# Power.net
KiCad netlist of a schematic drawn in Altium Designer
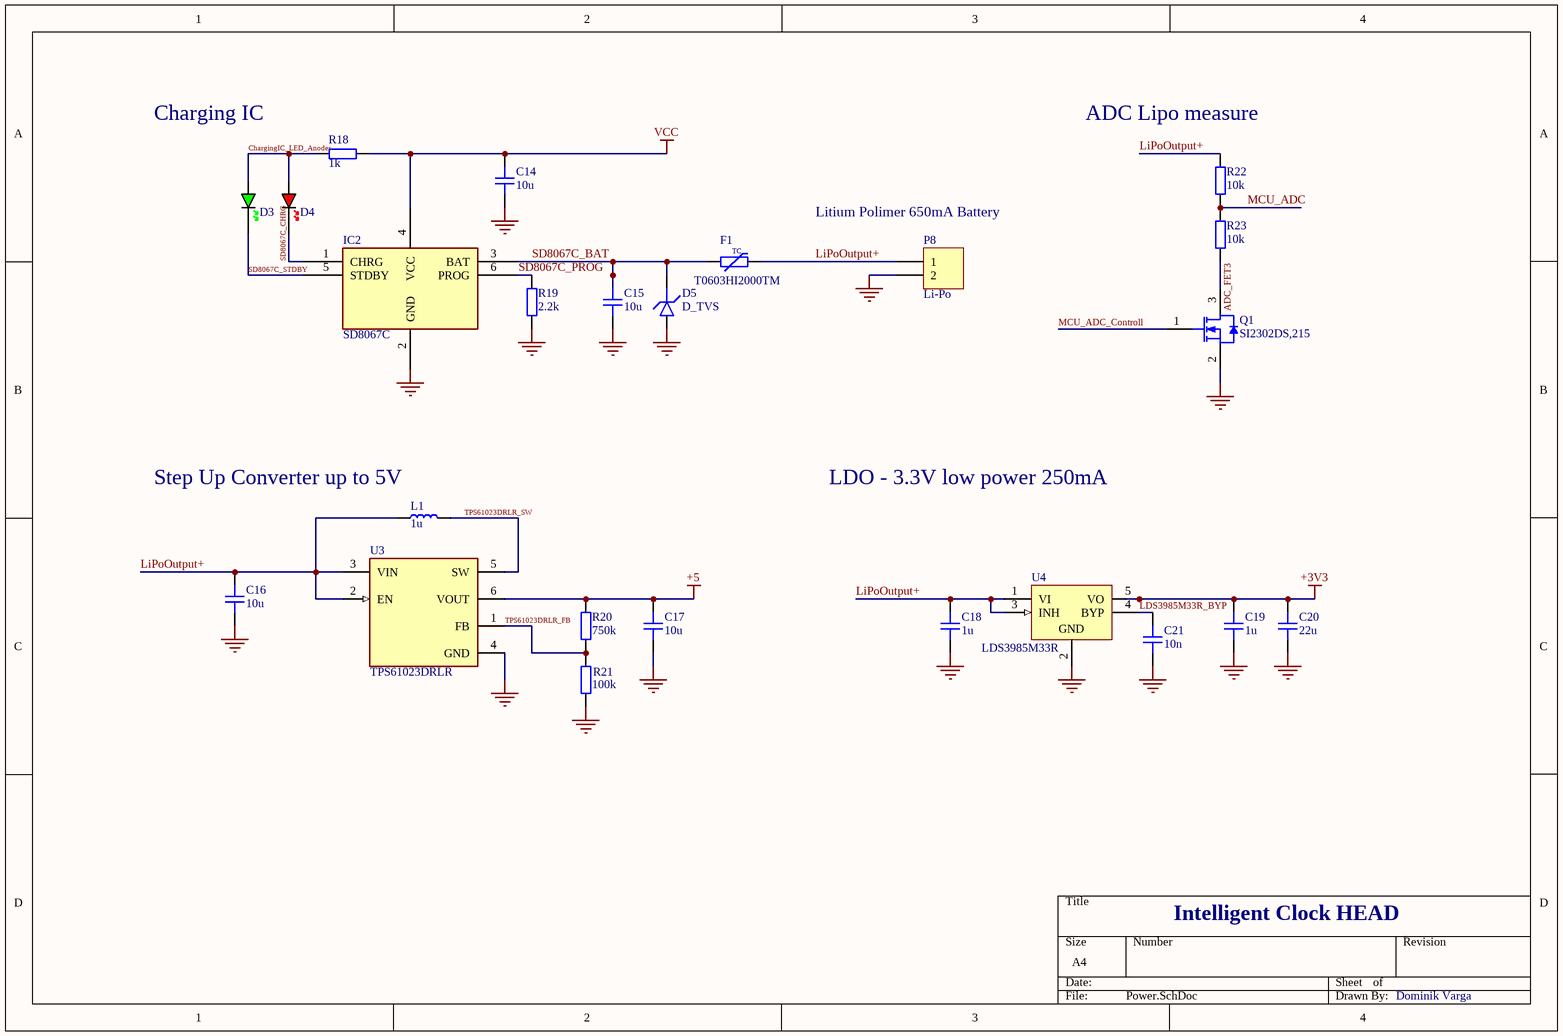
[diagram p0: Power.SchDoc]

(export (version "E")
  (design (tool "Eeschema 10.0.6"))
  (components
    (comp (ref "C14")
      (value "10u")
      (footprint "CAP_0603")
      (description "Capacitor SMD 0603 10V")
      (libsource (lib "Schematic-Lib-PhilsLab") (part "CAP_0603_10V"))
    )
    (comp (ref "C15")
      (value "10u")
      (footprint "CAP_0603")
      (description "Capacitor SMD 0603 10V")
      (libsource (lib "Schematic-Lib-PhilsLab") (part "CAP_0603_10V"))
    )
    (comp (ref "C16")
      (value "10u")
      (footprint "CAP_0603")
      (description "Capacitor SMD 0603 10V")
      (libsource (lib "Schematic-Lib-PhilsLab") (part "CAP_0603_10V"))
    )
    (comp (ref "C17")
      (value "10u")
      (footprint "CAP_0603")
      (description "Capacitor SMD 0603 10V")
      (libsource (lib "Schematic-Lib-PhilsLab") (part "CAP_0603_10V"))
    )
    (comp (ref "C18")
      (value "1u")
      (footprint "CAP_0603")
      (description "Capacitor SMD 0603 10V")
      (libsource (lib "Schematic-Lib-PhilsLab") (part "CAP_0603_10V"))
    )
    (comp (ref "C19")
      (value "1u")
      (footprint "CAP_0603")
      (description "Capacitor SMD 0603 10V")
      (libsource (lib "Schematic-Lib-PhilsLab") (part "CAP_0603_10V"))
    )
    (comp (ref "C20")
      (value "22u")
      (footprint "CAP_0603")
      (description "Capacitor SMD 0603 10V")
      (libsource (lib "Schematic-Lib-PhilsLab") (part "CAP_0603_10V"))
    )
    (comp (ref "C21")
      (value "10n")
      (footprint "CAP_0603")
      (description "Capacitor SMD 0603 10V")
      (libsource (lib "Schematic-Lib-PhilsLab") (part "CAP_0603_10V"))
    )
    (comp (ref "D3")
      (value "GREEN")
      (footprint "LED_0603_GREEN")
      (description "LED 0603 GREEN SMD")
      (libsource (lib "Schematic-Lib-PhilsLab") (part "LED_0603_GREEN"))
    )
    (comp (ref "D4")
      (value "RED")
      (footprint "LED_0603_RED")
      (description "LED 0603 RED SMD")
      (libsource (lib "Schematic-Lib-PhilsLab") (part "LED_0603_RED"))
    )
    (comp (ref "D5")
      (value "D_TVS")
      (footprint "DIOM2718X14N")
      (description "Diode TVS / ESD 0603")
      (libsource (lib "OnlabComponents") (part "D_TVS_0603"))
    )
    (comp (ref "F1")
      (value "T0603HI2000TM")
      (footprint "RESC1608X06N")
      (description "Fuse SMD 0603")
      (fields (field (name "MANUFACTURER") "AEM"))
      (libsource (lib "OnlabComponents") (part "FUSE_0603"))
    )
    (comp (ref "IC2")
      (value "SD8067C")
      (footprint "SOT95P280X125-6N")
      (description "Integrated Circuit, charging circuit")
      (fields (field (name "MANUFACTURER") "Shouding"))
      (libsource (lib "OnlabComponents") (part "SD8067C"))
    )
    (comp (ref "L1")
      (value "1u")
      (footprint "IND_1210")
      (description "Inductor SMD 1210")
      (libsource (lib "OnlabComponents") (part "IND_1210"))
    )
    (comp (ref "P8")
      (value "Li-Po")
      (footprint "HDR1X2H")
      (description "Header, 2-Pin, Right Angle")
      (fields (field (name "PUBLISHER") "Altium Limited"))
      (libsource (lib "Miscellaneous Connectors") (part "Header 2H"))
    )
    (comp (ref "Q1")
      (value "SI2302DS,215")
      (footprint "NXP-SOT23_N")
      (description "N-Channel Enhancement Mode Field-Effect Transistor, 20 V, 2.5 A, 3-Pin SOT23, Tape and Reel")
      (fields (field (name "MANUFACTURER") "NXP Semiconductors"))
      (libsource (lib "Altium Content Vault") (part "NXP-NMOS-GSD-3_B"))
    )
    (comp (ref "R18")
      (value "1k")
      (footprint "RES_0603")
      (description "Resistor SMD 0603")
      (libsource (lib "Schematic-Lib-PhilsLab") (part "RES_0603"))
    )
    (comp (ref "R19")
      (value "2.2k")
      (footprint "RES_0603")
      (description "Resistor SMD 0603")
      (libsource (lib "Schematic-Lib-PhilsLab") (part "RES_0603"))
    )
    (comp (ref "R20")
      (value "750k")
      (footprint "RES_0603")
      (description "Resistor SMD 0603")
      (libsource (lib "Schematic-Lib-PhilsLab") (part "RES_0603"))
    )
    (comp (ref "R21")
      (value "100k")
      (footprint "RES_0603")
      (description "Resistor SMD 0603")
      (libsource (lib "Schematic-Lib-PhilsLab") (part "RES_0603"))
    )
    (comp (ref "R22")
      (value "10k")
      (footprint "RES_0603")
      (description "Resistor SMD 0603")
      (libsource (lib "Schematic-Lib-PhilsLab") (part "RES_0603"))
    )
    (comp (ref "R23")
      (value "10k")
      (footprint "RES_0603")
      (description "Resistor SMD 0603")
      (libsource (lib "Schematic-Lib-PhilsLab") (part "RES_0603"))
    )
    (comp (ref "U3")
      (value "TPS61023DRLR")
      (footprint "FP-DRL0006A-MFG")
      (description "FINISH GOODS FOR TPS61023")
      (libsource (lib "Altium Content Vault") (part "b28b3e956a4ad07201ce69f9d09f9a8"))
    )
    (comp (ref "U4")
      (value "LDS3985M33R")
      (footprint "SOT23-5L_M")
      (libsource (lib "Altium Content Vault") (part "PM-REG-LD3985-SOT5"))
    )
  )
  (nets
    (net (code "1") (name "+3V3") (class "Default")
      (node (ref "C19") (pin "2") (pinfunction "2_2") (pintype "passive"))
      (node (ref "C20") (pin "2") (pinfunction "2_2") (pintype "passive"))
      (node (ref "U4") (pin "5") (pinfunction "VO_5") (pintype "power_in"))
    )
    (net (code "2") (name "+5") (class "Default")
      (node (ref "C17") (pin "2") (pinfunction "2_2") (pintype "passive"))
      (node (ref "R20") (pin "2") (pinfunction "2_2") (pintype "passive"))
      (node (ref "U3") (pin "6") (pinfunction "VOUT_6") (pintype "power_in"))
    )
    (net (code "3") (name "/ADC_FET3") (class "Default")
      (node (ref "Q1") (pin "3") (pinfunction "D_3") (pintype "passive"))
      (node (ref "R23") (pin "1") (pinfunction "1_1") (pintype "passive"))
    )
    (net (code "4") (name "/ChargingIC_LED_Anodes") (class "Default")
      (node (ref "D3") (pin "A") (pinfunction "A_A") (pintype "passive"))
      (node (ref "D4") (pin "A") (pinfunction "A_A") (pintype "passive"))
      (node (ref "R18") (pin "1") (pinfunction "1_1") (pintype "passive"))
    )
    (net (code "5") (name "/LDS3985M33R_BYP") (class "Default")
      (node (ref "C21") (pin "2") (pinfunction "2_2") (pintype "passive"))
      (node (ref "U4") (pin "4") (pinfunction "BYP_4") (pintype "passive"))
    )
    (net (code "6") (name "/LiPoOutput+") (class "Default")
      (node (ref "C16") (pin "2") (pinfunction "2_2") (pintype "passive"))
      (node (ref "C18") (pin "2") (pinfunction "2_2") (pintype "passive"))
      (node (ref "F1") (pin "2") (pinfunction "2_2") (pintype "passive"))
      (node (ref "L1") (pin "1") (pinfunction "1_1") (pintype "passive"))
      (node (ref "P8") (pin "1") (pinfunction "1_1") (pintype "passive"))
      (node (ref "R22") (pin "2") (pinfunction "2_2") (pintype "passive"))
      (node (ref "U3") (pin "2") (pinfunction "EN_2") (pintype "input"))
      (node (ref "U3") (pin "3") (pinfunction "VIN_3") (pintype "power_in"))
      (node (ref "U4") (pin "1") (pinfunction "VI_1") (pintype "power_in"))
      (node (ref "U4") (pin "3") (pinfunction "INH_3") (pintype "input"))
    )
    (net (code "7") (name "/MCU_ADC") (class "Default")
      (node (ref "R22") (pin "1") (pinfunction "1_1") (pintype "passive"))
      (node (ref "R23") (pin "2") (pinfunction "2_2") (pintype "passive"))
    )
    (net (code "8") (name "/MCU_ADC_Controll") (class "Default")
      (node (ref "Q1") (pin "1") (pinfunction "G_1") (pintype "passive"))
    )
    (net (code "9") (name "/SD8067C_BAT") (class "Default")
      (node (ref "C15") (pin "2") (pinfunction "2_2") (pintype "passive"))
      (node (ref "D5") (pin "1") (pinfunction "K_1") (pintype "passive"))
      (node (ref "F1") (pin "1") (pinfunction "1_1") (pintype "passive"))
      (node (ref "IC2") (pin "3") (pinfunction "BAT_3") (pintype "passive"))
    )
    (net (code "10") (name "/SD8067C_CHRG") (class "Default")
      (node (ref "D4") (pin "K") (pinfunction "K_K") (pintype "passive"))
      (node (ref "IC2") (pin "1") (pinfunction "CHRG_1") (pintype "passive"))
    )
    (net (code "11") (name "/SD8067C_PROG") (class "Default")
      (node (ref "IC2") (pin "6") (pinfunction "PROG_6") (pintype "passive"))
      (node (ref "R19") (pin "1") (pinfunction "1_1") (pintype "passive"))
    )
    (net (code "12") (name "/SD8067C_STDBY") (class "Default")
      (node (ref "D3") (pin "K") (pinfunction "K_K") (pintype "passive"))
      (node (ref "IC2") (pin "5") (pinfunction "STDBY_5") (pintype "passive"))
    )
    (net (code "13") (name "/TPS61023DRLR_FB") (class "Default")
      (node (ref "R20") (pin "1") (pinfunction "1_1") (pintype "passive"))
      (node (ref "R21") (pin "2") (pinfunction "2_2") (pintype "passive"))
      (node (ref "U3") (pin "1") (pinfunction "FB_1") (pintype "passive"))
    )
    (net (code "14") (name "/TPS61023DRLR_SW") (class "Default")
      (node (ref "L1") (pin "2") (pinfunction "2_2") (pintype "passive"))
      (node (ref "U3") (pin "5") (pinfunction "SW_5") (pintype "passive"))
    )
    (net (code "15") (name "GND") (class "Default")
      (node (ref "C14") (pin "1") (pinfunction "1_1") (pintype "passive"))
      (node (ref "C15") (pin "1") (pinfunction "1_1") (pintype "passive"))
      (node (ref "C16") (pin "1") (pinfunction "1_1") (pintype "passive"))
      (node (ref "C17") (pin "1") (pinfunction "1_1") (pintype "passive"))
      (node (ref "C18") (pin "1") (pinfunction "1_1") (pintype "passive"))
      (node (ref "C19") (pin "1") (pinfunction "1_1") (pintype "passive"))
      (node (ref "C20") (pin "1") (pinfunction "1_1") (pintype "passive"))
      (node (ref "C21") (pin "1") (pinfunction "1_1") (pintype "passive"))
      (node (ref "D5") (pin "2") (pinfunction "A_2") (pintype "passive"))
      (node (ref "IC2") (pin "2") (pinfunction "GND_2") (pintype "passive"))
      (node (ref "P8") (pin "2") (pinfunction "2_2") (pintype "passive"))
      (node (ref "Q1") (pin "2") (pinfunction "S_2") (pintype "passive"))
      (node (ref "R19") (pin "2") (pinfunction "2_2") (pintype "passive"))
      (node (ref "R21") (pin "1") (pinfunction "1_1") (pintype "passive"))
      (node (ref "U3") (pin "4") (pinfunction "GND_4") (pintype "power_in"))
      (node (ref "U4") (pin "2") (pinfunction "GND_2") (pintype "power_in"))
    )
    (net (code "16") (name "VCC") (class "Default")
      (node (ref "C14") (pin "2") (pinfunction "2_2") (pintype "passive"))
      (node (ref "IC2") (pin "4") (pinfunction "VCC_4") (pintype "passive"))
      (node (ref "R18") (pin "2") (pinfunction "2_2") (pintype "passive"))
    )
  )
)
